# 9_Pwm_Buffer.net
KiCad netlist of a schematic drawn in Altium Designer
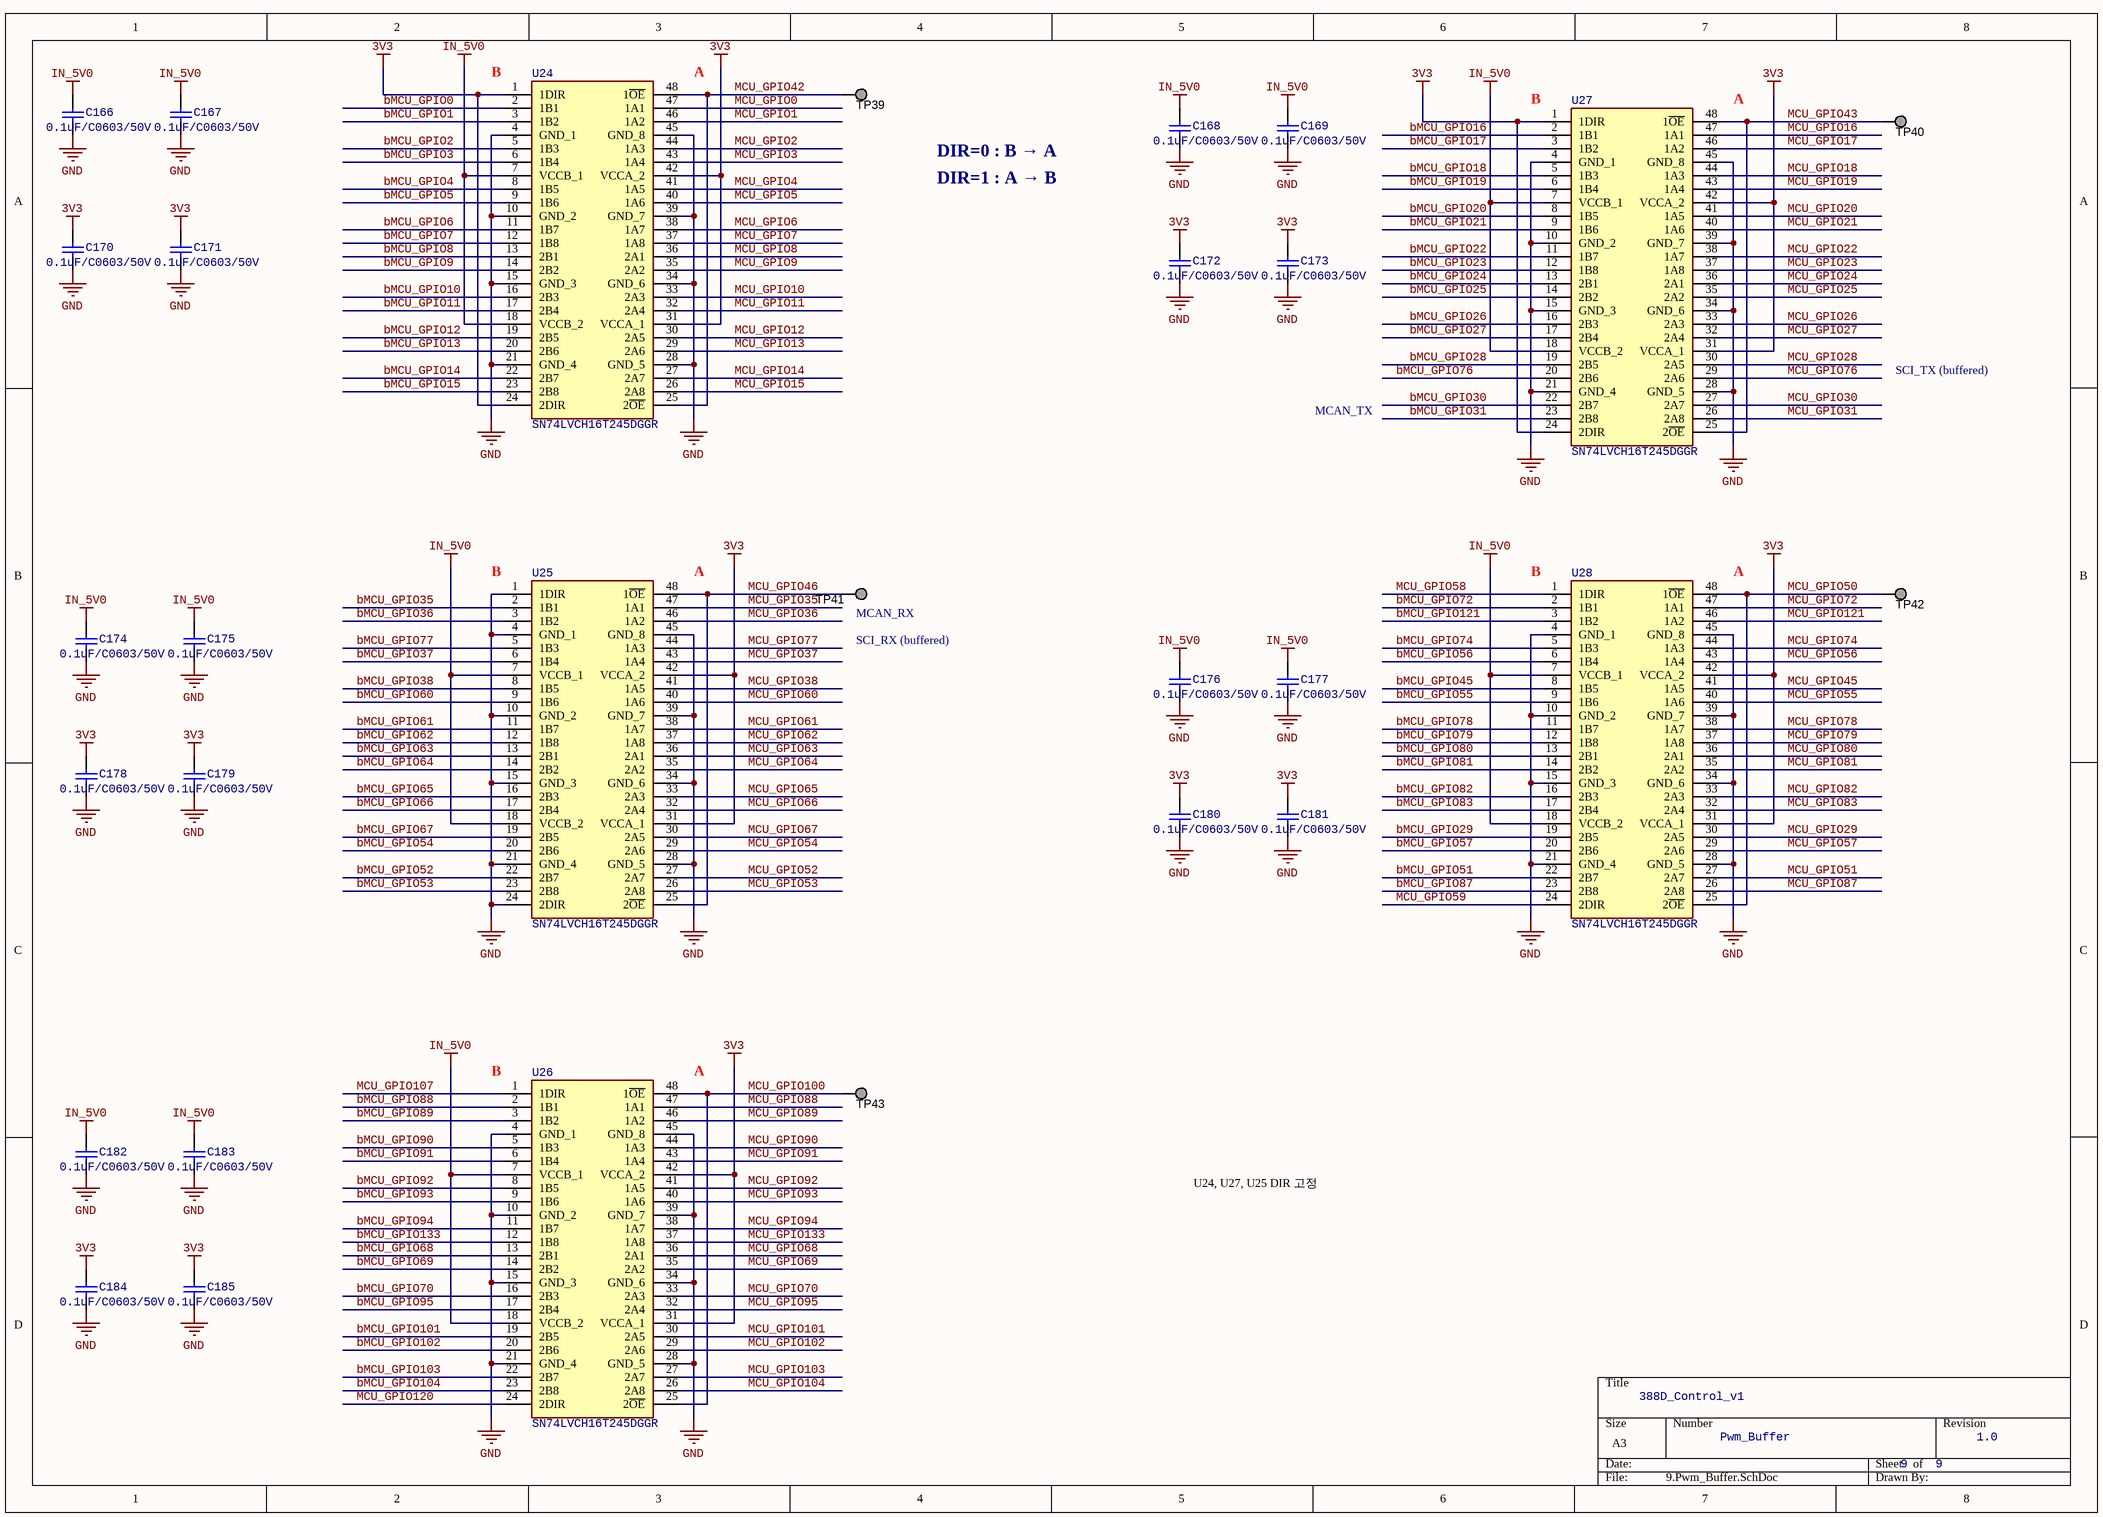
[diagram p0: 9.Pwm_Buffer.SchDoc]

(export (version "E")
  (design (tool "Eeschema 10.0.6"))
  (components
    (comp (ref "C166")
      (value "0.1uF/C0603/50V")
      (footprint "CAPC1608X90X40NL10T20")
      (description "Chip Capacitor, 100 nF, +/- 10%, 50 V, 0603 (1608 Metric)")
      (fields (field (name "TOLERANCE") "10%") (field (name "Comment") "Capacitor 100 nF +/-10% 50 V 0603"))
      (libsource (lib "PEETS_V2") (part "CAP-NP-2"))
    )
    (comp (ref "C167")
      (value "0.1uF/C0603/50V")
      (footprint "CAPC1608X90X40NL10T20")
      (description "Chip Capacitor, 100 nF, +/- 10%, 50 V, 0603 (1608 Metric)")
      (fields (field (name "TOLERANCE") "10%") (field (name "Comment") "Capacitor 100 nF +/-10% 50 V 0603"))
      (libsource (lib "PEETS_V2") (part "CAP-NP-2"))
    )
    (comp (ref "C168")
      (value "0.1uF/C0603/50V")
      (footprint "CAPC1608X90X40NL10T20")
      (description "Chip Capacitor, 100 nF, +/- 10%, 50 V, 0603 (1608 Metric)")
      (fields (field (name "TOLERANCE") "10%") (field (name "Comment") "Capacitor 100 nF +/-10% 50 V 0603"))
      (libsource (lib "PEETS_V2") (part "CAP-NP-2"))
    )
    (comp (ref "C169")
      (value "0.1uF/C0603/50V")
      (footprint "CAPC1608X90X40NL10T20")
      (description "Chip Capacitor, 100 nF, +/- 10%, 50 V, 0603 (1608 Metric)")
      (fields (field (name "TOLERANCE") "10%") (field (name "Comment") "Capacitor 100 nF +/-10% 50 V 0603"))
      (libsource (lib "PEETS_V2") (part "CAP-NP-2"))
    )
    (comp (ref "C170")
      (value "0.1uF/C0603/50V")
      (footprint "CAPC1608X90X40NL10T20")
      (description "Chip Capacitor, 100 nF, +/- 10%, 50 V, 0603 (1608 Metric)")
      (fields (field (name "TOLERANCE") "10%") (field (name "Comment") "Capacitor 100 nF +/-10% 50 V 0603"))
      (libsource (lib "PEETS_V2") (part "CAP-NP-2"))
    )
    (comp (ref "C171")
      (value "0.1uF/C0603/50V")
      (footprint "CAPC1608X90X40NL10T20")
      (description "Chip Capacitor, 100 nF, +/- 10%, 50 V, 0603 (1608 Metric)")
      (fields (field (name "TOLERANCE") "10%") (field (name "Comment") "Capacitor 100 nF +/-10% 50 V 0603"))
      (libsource (lib "PEETS_V2") (part "CAP-NP-2"))
    )
    (comp (ref "C172")
      (value "0.1uF/C0603/50V")
      (footprint "CAPC1608X90X40NL10T20")
      (description "Chip Capacitor, 100 nF, +/- 10%, 50 V, 0603 (1608 Metric)")
      (fields (field (name "TOLERANCE") "10%") (field (name "Comment") "Capacitor 100 nF +/-10% 50 V 0603"))
      (libsource (lib "PEETS_V2") (part "CAP-NP-2"))
    )
    (comp (ref "C173")
      (value "0.1uF/C0603/50V")
      (footprint "CAPC1608X90X40NL10T20")
      (description "Chip Capacitor, 100 nF, +/- 10%, 50 V, 0603 (1608 Metric)")
      (fields (field (name "TOLERANCE") "10%") (field (name "Comment") "Capacitor 100 nF +/-10% 50 V 0603"))
      (libsource (lib "PEETS_V2") (part "CAP-NP-2"))
    )
    (comp (ref "C174")
      (value "0.1uF/C0603/50V")
      (footprint "CAPC1608X90X40NL10T20")
      (description "Chip Capacitor, 100 nF, +/- 10%, 50 V, 0603 (1608 Metric)")
      (fields (field (name "TOLERANCE") "10%") (field (name "Comment") "Capacitor 100 nF +/-10% 50 V 0603"))
      (libsource (lib "PEETS_V2") (part "CAP-NP-2"))
    )
    (comp (ref "C175")
      (value "0.1uF/C0603/50V")
      (footprint "CAPC1608X90X40NL10T20")
      (description "Chip Capacitor, 100 nF, +/- 10%, 50 V, 0603 (1608 Metric)")
      (fields (field (name "TOLERANCE") "10%") (field (name "Comment") "Capacitor 100 nF +/-10% 50 V 0603"))
      (libsource (lib "PEETS_V2") (part "CAP-NP-2"))
    )
    (comp (ref "C176")
      (value "0.1uF/C0603/50V")
      (footprint "CAPC1608X90X40NL10T20")
      (description "Chip Capacitor, 100 nF, +/- 10%, 50 V, 0603 (1608 Metric)")
      (fields (field (name "TOLERANCE") "10%") (field (name "Comment") "Capacitor 100 nF +/-10% 50 V 0603"))
      (libsource (lib "PEETS_V2") (part "CAP-NP-2"))
    )
    (comp (ref "C177")
      (value "0.1uF/C0603/50V")
      (footprint "CAPC1608X90X40NL10T20")
      (description "Chip Capacitor, 100 nF, +/- 10%, 50 V, 0603 (1608 Metric)")
      (fields (field (name "TOLERANCE") "10%") (field (name "Comment") "Capacitor 100 nF +/-10% 50 V 0603"))
      (libsource (lib "PEETS_V2") (part "CAP-NP-2"))
    )
    (comp (ref "C178")
      (value "0.1uF/C0603/50V")
      (footprint "CAPC1608X90X40NL10T20")
      (description "Chip Capacitor, 100 nF, +/- 10%, 50 V, 0603 (1608 Metric)")
      (fields (field (name "TOLERANCE") "10%") (field (name "Comment") "Capacitor 100 nF +/-10% 50 V 0603"))
      (libsource (lib "PEETS_V2") (part "CAP-NP-2"))
    )
    (comp (ref "C179")
      (value "0.1uF/C0603/50V")
      (footprint "CAPC1608X90X40NL10T20")
      (description "Chip Capacitor, 100 nF, +/- 10%, 50 V, 0603 (1608 Metric)")
      (fields (field (name "TOLERANCE") "10%") (field (name "Comment") "Capacitor 100 nF +/-10% 50 V 0603"))
      (libsource (lib "PEETS_V2") (part "CAP-NP-2"))
    )
    (comp (ref "C180")
      (value "0.1uF/C0603/50V")
      (footprint "CAPC1608X90X40NL10T20")
      (description "Chip Capacitor, 100 nF, +/- 10%, 50 V, 0603 (1608 Metric)")
      (fields (field (name "TOLERANCE") "10%") (field (name "Comment") "Capacitor 100 nF +/-10% 50 V 0603"))
      (libsource (lib "PEETS_V2") (part "CAP-NP-2"))
    )
    (comp (ref "C181")
      (value "0.1uF/C0603/50V")
      (footprint "CAPC1608X90X40NL10T20")
      (description "Chip Capacitor, 100 nF, +/- 10%, 50 V, 0603 (1608 Metric)")
      (fields (field (name "TOLERANCE") "10%") (field (name "Comment") "Capacitor 100 nF +/-10% 50 V 0603"))
      (libsource (lib "PEETS_V2") (part "CAP-NP-2"))
    )
    (comp (ref "C182")
      (value "0.1uF/C0603/50V")
      (footprint "CAPC1608X90X40NL10T20")
      (description "Chip Capacitor, 100 nF, +/- 10%, 50 V, 0603 (1608 Metric)")
      (fields (field (name "TOLERANCE") "10%") (field (name "Comment") "Capacitor 100 nF +/-10% 50 V 0603"))
      (libsource (lib "PEETS_V2") (part "CAP-NP-2"))
    )
    (comp (ref "C183")
      (value "0.1uF/C0603/50V")
      (footprint "CAPC1608X90X40NL10T20")
      (description "Chip Capacitor, 100 nF, +/- 10%, 50 V, 0603 (1608 Metric)")
      (fields (field (name "TOLERANCE") "10%") (field (name "Comment") "Capacitor 100 nF +/-10% 50 V 0603"))
      (libsource (lib "PEETS_V2") (part "CAP-NP-2"))
    )
    (comp (ref "C184")
      (value "0.1uF/C0603/50V")
      (footprint "CAPC1608X90X40NL10T20")
      (description "Chip Capacitor, 100 nF, +/- 10%, 50 V, 0603 (1608 Metric)")
      (fields (field (name "TOLERANCE") "10%") (field (name "Comment") "Capacitor 100 nF +/-10% 50 V 0603"))
      (libsource (lib "PEETS_V2") (part "CAP-NP-2"))
    )
    (comp (ref "C185")
      (value "0.1uF/C0603/50V")
      (footprint "CAPC1608X90X40NL10T20")
      (description "Chip Capacitor, 100 nF, +/- 10%, 50 V, 0603 (1608 Metric)")
      (fields (field (name "TOLERANCE") "10%") (field (name "Comment") "Capacitor 100 nF +/-10% 50 V 0603"))
      (libsource (lib "PEETS_V2") (part "CAP-NP-2"))
    )
    (comp (ref "TP39")
      (value "TESTPOINT")
      (footprint "TP_50MIL-25MILHOLE")
      (description "TEST POINT.  No entry in BOM.")
      (libsource (lib "388D_Control_v1") (part "CMP-0078143-3"))
    )
    (comp (ref "TP40")
      (value "TESTPOINT")
      (footprint "TP_50MIL-25MILHOLE")
      (description "TEST POINT.  No entry in BOM.")
      (libsource (lib "388D_Control_v1") (part "CMP-0078143-3"))
    )
    (comp (ref "TP41")
      (value "TESTPOINT")
      (footprint "TP_50MIL-25MILHOLE")
      (description "TEST POINT.  No entry in BOM.")
      (libsource (lib "388D_Control_v1") (part "CMP-0078143-3"))
    )
    (comp (ref "TP42")
      (value "TESTPOINT")
      (footprint "TP_50MIL-25MILHOLE")
      (description "TEST POINT.  No entry in BOM.")
      (libsource (lib "388D_Control_v1") (part "CMP-0078143-3"))
    )
    (comp (ref "TP43")
      (value "TESTPOINT")
      (footprint "TP_50MIL-25MILHOLE")
      (description "TEST POINT.  No entry in BOM.")
      (libsource (lib "388D_Control_v1") (part "CMP-0078143-3"))
    )
    (comp (ref "U24")
      (value "SN74LVCH16T245DGGR")
      (footprint "SOP50P810X120-48N")
      (description "16-Bit Dual-Supply Bus Transceiver")
      (fields (field (name "MOUSER PART NUMBER") "595-SN74LVCH16T245GR"))
      (libsource (lib "PEETS_V2") (part "SN74LVCH16T245DGGR"))
    )
    (comp (ref "U25")
      (value "SN74LVCH16T245DGGR")
      (footprint "SOP50P810X120-48N")
      (description "16-Bit Dual-Supply Bus Transceiver")
      (fields (field (name "MOUSER PART NUMBER") "595-SN74LVCH16T245GR"))
      (libsource (lib "PEETS_V2") (part "SN74LVCH16T245DGGR"))
    )
    (comp (ref "U26")
      (value "SN74LVCH16T245DGGR")
      (footprint "SOP50P810X120-48N")
      (description "16-Bit Dual-Supply Bus Transceiver")
      (fields (field (name "MOUSER PART NUMBER") "595-SN74LVCH16T245GR"))
      (libsource (lib "PEETS_V2") (part "SN74LVCH16T245DGGR"))
    )
    (comp (ref "U27")
      (value "SN74LVCH16T245DGGR")
      (footprint "SOP50P810X120-48N")
      (description "16-Bit Dual-Supply Bus Transceiver")
      (fields (field (name "MOUSER PART NUMBER") "595-SN74LVCH16T245GR"))
      (libsource (lib "PEETS_V2") (part "SN74LVCH16T245DGGR"))
    )
    (comp (ref "U28")
      (value "SN74LVCH16T245DGGR")
      (footprint "SOP50P810X120-48N")
      (description "16-Bit Dual-Supply Bus Transceiver")
      (fields (field (name "MOUSER PART NUMBER") "595-SN74LVCH16T245GR"))
      (libsource (lib "PEETS_V2") (part "SN74LVCH16T245DGGR"))
    )
  )
  (nets
    (net (code "1") (name "/MCU_GPIO0") (class "Default")
      (node (ref "U24") (pin "47") (pinfunction "1A1_47") (pintype "passive"))
    )
    (net (code "2") (name "/MCU_GPIO1") (class "Default")
      (node (ref "U24") (pin "46") (pinfunction "1A2_46") (pintype "passive"))
    )
    (net (code "3") (name "/MCU_GPIO2") (class "Default")
      (node (ref "U24") (pin "44") (pinfunction "1A3_44") (pintype "passive"))
    )
    (net (code "4") (name "/MCU_GPIO3") (class "Default")
      (node (ref "U24") (pin "43") (pinfunction "1A4_43") (pintype "passive"))
    )
    (net (code "5") (name "/MCU_GPIO4") (class "Default")
      (node (ref "U24") (pin "41") (pinfunction "1A5_41") (pintype "passive"))
    )
    (net (code "6") (name "/MCU_GPIO5") (class "Default")
      (node (ref "U24") (pin "40") (pinfunction "1A6_40") (pintype "passive"))
    )
    (net (code "7") (name "/MCU_GPIO6") (class "Default")
      (node (ref "U24") (pin "38") (pinfunction "1A7_38") (pintype "passive"))
    )
    (net (code "8") (name "/MCU_GPIO7") (class "Default")
      (node (ref "U24") (pin "37") (pinfunction "1A8_37") (pintype "passive"))
    )
    (net (code "9") (name "/MCU_GPIO8") (class "Default")
      (node (ref "U24") (pin "36") (pinfunction "2A1_36") (pintype "passive"))
    )
    (net (code "10") (name "/MCU_GPIO9") (class "Default")
      (node (ref "U24") (pin "35") (pinfunction "2A2_35") (pintype "passive"))
    )
    (net (code "11") (name "/MCU_GPIO10") (class "Default")
      (node (ref "U24") (pin "33") (pinfunction "2A3_33") (pintype "passive"))
    )
    (net (code "12") (name "/MCU_GPIO11") (class "Default")
      (node (ref "U24") (pin "32") (pinfunction "2A4_32") (pintype "passive"))
    )
    (net (code "13") (name "/MCU_GPIO12") (class "Default")
      (node (ref "U24") (pin "30") (pinfunction "2A5_30") (pintype "passive"))
    )
    (net (code "14") (name "/MCU_GPIO13") (class "Default")
      (node (ref "U24") (pin "29") (pinfunction "2A6_29") (pintype "passive"))
    )
    (net (code "15") (name "/MCU_GPIO14") (class "Default")
      (node (ref "U24") (pin "27") (pinfunction "2A7_27") (pintype "passive"))
    )
    (net (code "16") (name "/MCU_GPIO15") (class "Default")
      (node (ref "U24") (pin "26") (pinfunction "2A8_26") (pintype "passive"))
    )
    (net (code "17") (name "/MCU_GPIO16") (class "Default")
      (node (ref "U27") (pin "47") (pinfunction "1A1_47") (pintype "passive"))
    )
    (net (code "18") (name "/MCU_GPIO17") (class "Default")
      (node (ref "U27") (pin "46") (pinfunction "1A2_46") (pintype "passive"))
    )
    (net (code "19") (name "/MCU_GPIO18") (class "Default")
      (node (ref "U27") (pin "44") (pinfunction "1A3_44") (pintype "passive"))
    )
    (net (code "20") (name "/MCU_GPIO19") (class "Default")
      (node (ref "U27") (pin "43") (pinfunction "1A4_43") (pintype "passive"))
    )
    (net (code "21") (name "/MCU_GPIO20") (class "Default")
      (node (ref "U27") (pin "41") (pinfunction "1A5_41") (pintype "passive"))
    )
    (net (code "22") (name "/MCU_GPIO21") (class "Default")
      (node (ref "U27") (pin "40") (pinfunction "1A6_40") (pintype "passive"))
    )
    (net (code "23") (name "/MCU_GPIO22") (class "Default")
      (node (ref "U27") (pin "38") (pinfunction "1A7_38") (pintype "passive"))
    )
    (net (code "24") (name "/MCU_GPIO23") (class "Default")
      (node (ref "U27") (pin "37") (pinfunction "1A8_37") (pintype "passive"))
    )
    (net (code "25") (name "/MCU_GPIO24") (class "Default")
      (node (ref "U27") (pin "36") (pinfunction "2A1_36") (pintype "passive"))
    )
    (net (code "26") (name "/MCU_GPIO25") (class "Default")
      (node (ref "U27") (pin "35") (pinfunction "2A2_35") (pintype "passive"))
    )
    (net (code "27") (name "/MCU_GPIO26") (class "Default")
      (node (ref "U27") (pin "33") (pinfunction "2A3_33") (pintype "passive"))
    )
    (net (code "28") (name "/MCU_GPIO27") (class "Default")
      (node (ref "U27") (pin "32") (pinfunction "2A4_32") (pintype "passive"))
    )
    (net (code "29") (name "/MCU_GPIO28") (class "Default")
      (node (ref "U27") (pin "30") (pinfunction "2A5_30") (pintype "passive"))
    )
    (net (code "30") (name "/MCU_GPIO29") (class "Default")
      (node (ref "U28") (pin "30") (pinfunction "2A5_30") (pintype "passive"))
    )
    (net (code "31") (name "/MCU_GPIO30") (class "Default")
      (node (ref "U27") (pin "27") (pinfunction "2A7_27") (pintype "passive"))
    )
    (net (code "32") (name "/MCU_GPIO31") (class "Default")
      (node (ref "U27") (pin "26") (pinfunction "2A8_26") (pintype "passive"))
    )
    (net (code "33") (name "/MCU_GPIO35") (class "Default")
      (node (ref "U25") (pin "47") (pinfunction "1A1_47") (pintype "passive"))
    )
    (net (code "34") (name "/MCU_GPIO36") (class "Default")
      (node (ref "U25") (pin "46") (pinfunction "1A2_46") (pintype "passive"))
    )
    (net (code "35") (name "/MCU_GPIO37") (class "Default")
      (node (ref "U25") (pin "43") (pinfunction "1A4_43") (pintype "passive"))
    )
    (net (code "36") (name "/MCU_GPIO38") (class "Default")
      (node (ref "U25") (pin "41") (pinfunction "1A5_41") (pintype "passive"))
    )
    (net (code "37") (name "/MCU_GPIO42") (class "Default")
      (node (ref "TP39") (pin "1") (pintype "passive"))
      (node (ref "U24") (pin "25") (pinfunction "2~{OE}_25") (pintype "passive"))
      (node (ref "U24") (pin "48") (pinfunction "1~{OE}_48") (pintype "passive"))
    )
    (net (code "38") (name "/MCU_GPIO43") (class "Default")
      (node (ref "TP40") (pin "1") (pintype "passive"))
      (node (ref "U27") (pin "25") (pinfunction "2~{OE}_25") (pintype "passive"))
      (node (ref "U27") (pin "48") (pinfunction "1~{OE}_48") (pintype "passive"))
    )
    (net (code "39") (name "/MCU_GPIO45") (class "Default")
      (node (ref "U28") (pin "41") (pinfunction "1A5_41") (pintype "passive"))
    )
    (net (code "40") (name "/MCU_GPIO46") (class "Default")
      (node (ref "TP41") (pin "1") (pintype "passive"))
      (node (ref "U25") (pin "25") (pinfunction "2~{OE}_25") (pintype "passive"))
      (node (ref "U25") (pin "48") (pinfunction "1~{OE}_48") (pintype "passive"))
    )
    (net (code "41") (name "/MCU_GPIO50") (class "Default")
      (node (ref "TP42") (pin "1") (pintype "passive"))
      (node (ref "U28") (pin "25") (pinfunction "2~{OE}_25") (pintype "passive"))
      (node (ref "U28") (pin "48") (pinfunction "1~{OE}_48") (pintype "passive"))
    )
    (net (code "42") (name "/MCU_GPIO51") (class "Default")
      (node (ref "U28") (pin "27") (pinfunction "2A7_27") (pintype "passive"))
    )
    (net (code "43") (name "/MCU_GPIO52") (class "Default")
      (node (ref "U25") (pin "27") (pinfunction "2A7_27") (pintype "passive"))
    )
    (net (code "44") (name "/MCU_GPIO53") (class "Default")
      (node (ref "U25") (pin "26") (pinfunction "2A8_26") (pintype "passive"))
    )
    (net (code "45") (name "/MCU_GPIO54") (class "Default")
      (node (ref "U25") (pin "29") (pinfunction "2A6_29") (pintype "passive"))
    )
    (net (code "46") (name "/MCU_GPIO55") (class "Default")
      (node (ref "U28") (pin "40") (pinfunction "1A6_40") (pintype "passive"))
    )
    (net (code "47") (name "/MCU_GPIO56") (class "Default")
      (node (ref "U28") (pin "43") (pinfunction "1A4_43") (pintype "passive"))
    )
    (net (code "48") (name "/MCU_GPIO57") (class "Default")
      (node (ref "U28") (pin "29") (pinfunction "2A6_29") (pintype "passive"))
    )
    (net (code "49") (name "/MCU_GPIO58") (class "Default")
      (node (ref "U28") (pin "1") (pinfunction "1DIR_1") (pintype "passive"))
    )
    (net (code "50") (name "/MCU_GPIO59") (class "Default")
      (node (ref "U28") (pin "24") (pinfunction "2DIR_24") (pintype "passive"))
    )
    (net (code "51") (name "/MCU_GPIO60") (class "Default")
      (node (ref "U25") (pin "40") (pinfunction "1A6_40") (pintype "passive"))
    )
    (net (code "52") (name "/MCU_GPIO61") (class "Default")
      (node (ref "U25") (pin "38") (pinfunction "1A7_38") (pintype "passive"))
    )
    (net (code "53") (name "/MCU_GPIO62") (class "Default")
      (node (ref "U25") (pin "37") (pinfunction "1A8_37") (pintype "passive"))
    )
    (net (code "54") (name "/MCU_GPIO63") (class "Default")
      (node (ref "U25") (pin "36") (pinfunction "2A1_36") (pintype "passive"))
    )
    (net (code "55") (name "/MCU_GPIO64") (class "Default")
      (node (ref "U25") (pin "35") (pinfunction "2A2_35") (pintype "passive"))
    )
    (net (code "56") (name "/MCU_GPIO65") (class "Default")
      (node (ref "U25") (pin "33") (pinfunction "2A3_33") (pintype "passive"))
    )
    (net (code "57") (name "/MCU_GPIO66") (class "Default")
      (node (ref "U25") (pin "32") (pinfunction "2A4_32") (pintype "passive"))
    )
    (net (code "58") (name "/MCU_GPIO67") (class "Default")
      (node (ref "U25") (pin "30") (pinfunction "2A5_30") (pintype "passive"))
    )
    (net (code "59") (name "/MCU_GPIO68") (class "Default")
      (node (ref "U26") (pin "36") (pinfunction "2A1_36") (pintype "passive"))
    )
    (net (code "60") (name "/MCU_GPIO69") (class "Default")
      (node (ref "U26") (pin "35") (pinfunction "2A2_35") (pintype "passive"))
    )
    (net (code "61") (name "/MCU_GPIO70") (class "Default")
      (node (ref "U26") (pin "33") (pinfunction "2A3_33") (pintype "passive"))
    )
    (net (code "62") (name "/MCU_GPIO72") (class "Default")
      (node (ref "U28") (pin "47") (pinfunction "1A1_47") (pintype "passive"))
    )
    (net (code "63") (name "/MCU_GPIO74") (class "Default")
      (node (ref "U28") (pin "44") (pinfunction "1A3_44") (pintype "passive"))
    )
    (net (code "64") (name "/MCU_GPIO76") (class "Default")
      (node (ref "U27") (pin "29") (pinfunction "2A6_29") (pintype "passive"))
    )
    (net (code "65") (name "/MCU_GPIO77") (class "Default")
      (node (ref "U25") (pin "44") (pinfunction "1A3_44") (pintype "passive"))
    )
    (net (code "66") (name "/MCU_GPIO78") (class "Default")
      (node (ref "U28") (pin "38") (pinfunction "1A7_38") (pintype "passive"))
    )
    (net (code "67") (name "/MCU_GPIO79") (class "Default")
      (node (ref "U28") (pin "37") (pinfunction "1A8_37") (pintype "passive"))
    )
    (net (code "68") (name "/MCU_GPIO80") (class "Default")
      (node (ref "U28") (pin "36") (pinfunction "2A1_36") (pintype "passive"))
    )
    (net (code "69") (name "/MCU_GPIO81") (class "Default")
      (node (ref "U28") (pin "35") (pinfunction "2A2_35") (pintype "passive"))
    )
    (net (code "70") (name "/MCU_GPIO82") (class "Default")
      (node (ref "U28") (pin "33") (pinfunction "2A3_33") (pintype "passive"))
    )
    (net (code "71") (name "/MCU_GPIO83") (class "Default")
      (node (ref "U28") (pin "32") (pinfunction "2A4_32") (pintype "passive"))
    )
    (net (code "72") (name "/MCU_GPIO87") (class "Default")
      (node (ref "U28") (pin "26") (pinfunction "2A8_26") (pintype "passive"))
    )
    (net (code "73") (name "/MCU_GPIO88") (class "Default")
      (node (ref "U26") (pin "47") (pinfunction "1A1_47") (pintype "passive"))
    )
    (net (code "74") (name "/MCU_GPIO89") (class "Default")
      (node (ref "U26") (pin "46") (pinfunction "1A2_46") (pintype "passive"))
    )
    (net (code "75") (name "/MCU_GPIO90") (class "Default")
      (node (ref "U26") (pin "44") (pinfunction "1A3_44") (pintype "passive"))
    )
    (net (code "76") (name "/MCU_GPIO91") (class "Default")
      (node (ref "U26") (pin "43") (pinfunction "1A4_43") (pintype "passive"))
    )
    (net (code "77") (name "/MCU_GPIO92") (class "Default")
      (node (ref "U26") (pin "41") (pinfunction "1A5_41") (pintype "passive"))
    )
    (net (code "78") (name "/MCU_GPIO93") (class "Default")
      (node (ref "U26") (pin "40") (pinfunction "1A6_40") (pintype "passive"))
    )
    (net (code "79") (name "/MCU_GPIO94") (class "Default")
      (node (ref "U26") (pin "38") (pinfunction "1A7_38") (pintype "passive"))
    )
    (net (code "80") (name "/MCU_GPIO95") (class "Default")
      (node (ref "U26") (pin "32") (pinfunction "2A4_32") (pintype "passive"))
    )
    (net (code "81") (name "/MCU_GPIO100") (class "Default")
      (node (ref "TP43") (pin "1") (pintype "passive"))
      (node (ref "U26") (pin "25") (pinfunction "2~{OE}_25") (pintype "passive"))
      (node (ref "U26") (pin "48") (pinfunction "1~{OE}_48") (pintype "passive"))
    )
    (net (code "82") (name "/MCU_GPIO101") (class "Default")
      (node (ref "U26") (pin "30") (pinfunction "2A5_30") (pintype "passive"))
    )
    (net (code "83") (name "/MCU_GPIO102") (class "Default")
      (node (ref "U26") (pin "29") (pinfunction "2A6_29") (pintype "passive"))
    )
    (net (code "84") (name "/MCU_GPIO103") (class "Default")
      (node (ref "U26") (pin "27") (pinfunction "2A7_27") (pintype "passive"))
    )
    (net (code "85") (name "/MCU_GPIO104") (class "Default")
      (node (ref "U26") (pin "26") (pinfunction "2A8_26") (pintype "passive"))
    )
    (net (code "86") (name "/MCU_GPIO107") (class "Default")
      (node (ref "U26") (pin "1") (pinfunction "1DIR_1") (pintype "passive"))
    )
    (net (code "87") (name "/MCU_GPIO120") (class "Default")
      (node (ref "U26") (pin "24") (pinfunction "2DIR_24") (pintype "passive"))
    )
    (net (code "88") (name "/MCU_GPIO121") (class "Default")
      (node (ref "U28") (pin "46") (pinfunction "1A2_46") (pintype "passive"))
    )
    (net (code "89") (name "/MCU_GPIO133") (class "Default")
      (node (ref "U26") (pin "37") (pinfunction "1A8_37") (pintype "passive"))
    )
    (net (code "90") (name "/bMCU_GPIO0") (class "Default")
      (node (ref "U24") (pin "2") (pinfunction "1B1_2") (pintype "passive"))
    )
    (net (code "91") (name "/bMCU_GPIO1") (class "Default")
      (node (ref "U24") (pin "3") (pinfunction "1B2_3") (pintype "passive"))
    )
    (net (code "92") (name "/bMCU_GPIO2") (class "Default")
      (node (ref "U24") (pin "5") (pinfunction "1B3_5") (pintype "passive"))
    )
    (net (code "93") (name "/bMCU_GPIO3") (class "Default")
      (node (ref "U24") (pin "6") (pinfunction "1B4_6") (pintype "passive"))
    )
    (net (code "94") (name "/bMCU_GPIO4") (class "Default")
      (node (ref "U24") (pin "8") (pinfunction "1B5_8") (pintype "passive"))
    )
    (net (code "95") (name "/bMCU_GPIO5") (class "Default")
      (node (ref "U24") (pin "9") (pinfunction "1B6_9") (pintype "passive"))
    )
    (net (code "96") (name "/bMCU_GPIO6") (class "Default")
      (node (ref "U24") (pin "11") (pinfunction "1B7_11") (pintype "passive"))
    )
    (net (code "97") (name "/bMCU_GPIO7") (class "Default")
      (node (ref "U24") (pin "12") (pinfunction "1B8_12") (pintype "passive"))
    )
    (net (code "98") (name "/bMCU_GPIO8") (class "Default")
      (node (ref "U24") (pin "13") (pinfunction "2B1_13") (pintype "passive"))
    )
    (net (code "99") (name "/bMCU_GPIO9") (class "Default")
      (node (ref "U24") (pin "14") (pinfunction "2B2_14") (pintype "passive"))
    )
    (net (code "100") (name "/bMCU_GPIO10") (class "Default")
      (node (ref "U24") (pin "16") (pinfunction "2B3_16") (pintype "passive"))
    )
    (net (code "101") (name "/bMCU_GPIO11") (class "Default")
      (node (ref "U24") (pin "17") (pinfunction "2B4_17") (pintype "passive"))
    )
    (net (code "102") (name "/bMCU_GPIO12") (class "Default")
      (node (ref "U24") (pin "19") (pinfunction "2B5_19") (pintype "passive"))
    )
    (net (code "103") (name "/bMCU_GPIO13") (class "Default")
      (node (ref "U24") (pin "20") (pinfunction "2B6_20") (pintype "passive"))
    )
    (net (code "104") (name "/bMCU_GPIO14") (class "Default")
      (node (ref "U24") (pin "22") (pinfunction "2B7_22") (pintype "passive"))
    )
    (net (code "105") (name "/bMCU_GPIO15") (class "Default")
      (node (ref "U24") (pin "23") (pinfunction "2B8_23") (pintype "passive"))
    )
    (net (code "106") (name "/bMCU_GPIO16") (class "Default")
      (node (ref "U27") (pin "2") (pinfunction "1B1_2") (pintype "passive"))
    )
    (net (code "107") (name "/bMCU_GPIO17") (class "Default")
      (node (ref "U27") (pin "3") (pinfunction "1B2_3") (pintype "passive"))
    )
    (net (code "108") (name "/bMCU_GPIO18") (class "Default")
      (node (ref "U27") (pin "5") (pinfunction "1B3_5") (pintype "passive"))
    )
    (net (code "109") (name "/bMCU_GPIO19") (class "Default")
      (node (ref "U27") (pin "6") (pinfunction "1B4_6") (pintype "passive"))
    )
    (net (code "110") (name "/bMCU_GPIO20") (class "Default")
      (node (ref "U27") (pin "8") (pinfunction "1B5_8") (pintype "passive"))
    )
    (net (code "111") (name "/bMCU_GPIO21") (class "Default")
      (node (ref "U27") (pin "9") (pinfunction "1B6_9") (pintype "passive"))
    )
    (net (code "112") (name "/bMCU_GPIO22") (class "Default")
      (node (ref "U27") (pin "11") (pinfunction "1B7_11") (pintype "passive"))
    )
    (net (code "113") (name "/bMCU_GPIO23") (class "Default")
      (node (ref "U27") (pin "12") (pinfunction "1B8_12") (pintype "passive"))
    )
    (net (code "114") (name "/bMCU_GPIO24") (class "Default")
      (node (ref "U27") (pin "13") (pinfunction "2B1_13") (pintype "passive"))
    )
    (net (code "115") (name "/bMCU_GPIO25") (class "Default")
      (node (ref "U27") (pin "14") (pinfunction "2B2_14") (pintype "passive"))
    )
    (net (code "116") (name "/bMCU_GPIO26") (class "Default")
      (node (ref "U27") (pin "16") (pinfunction "2B3_16") (pintype "passive"))
    )
    (net (code "117") (name "/bMCU_GPIO27") (class "Default")
      (node (ref "U27") (pin "17") (pinfunction "2B4_17") (pintype "passive"))
    )
    (net (code "118") (name "/bMCU_GPIO28") (class "Default")
      (node (ref "U27") (pin "19") (pinfunction "2B5_19") (pintype "passive"))
    )
    (net (code "119") (name "/bMCU_GPIO29") (class "Default")
      (node (ref "U28") (pin "19") (pinfunction "2B5_19") (pintype "passive"))
    )
    (net (code "120") (name "/bMCU_GPIO30") (class "Default")
      (node (ref "U27") (pin "22") (pinfunction "2B7_22") (pintype "passive"))
    )
    (net (code "121") (name "/bMCU_GPIO31") (class "Default")
      (node (ref "U27") (pin "23") (pinfunction "2B8_23") (pintype "passive"))
    )
    (net (code "122") (name "/bMCU_GPIO35") (class "Default")
      (node (ref "U25") (pin "2") (pinfunction "1B1_2") (pintype "passive"))
    )
    (net (code "123") (name "/bMCU_GPIO36") (class "Default")
      (node (ref "U25") (pin "3") (pinfunction "1B2_3") (pintype "passive"))
    )
    (net (code "124") (name "/bMCU_GPIO37") (class "Default")
      (node (ref "U25") (pin "6") (pinfunction "1B4_6") (pintype "passive"))
    )
    (net (code "125") (name "/bMCU_GPIO38") (class "Default")
      (node (ref "U25") (pin "8") (pinfunction "1B5_8") (pintype "passive"))
    )
    (net (code "126") (name "/bMCU_GPIO45") (class "Default")
      (node (ref "U28") (pin "8") (pinfunction "1B5_8") (pintype "passive"))
    )
    (net (code "127") (name "/bMCU_GPIO51") (class "Default")
      (node (ref "U28") (pin "22") (pinfunction "2B7_22") (pintype "passive"))
    )
    (net (code "128") (name "/bMCU_GPIO52") (class "Default")
      (node (ref "U25") (pin "22") (pinfunction "2B7_22") (pintype "passive"))
    )
    (net (code "129") (name "/bMCU_GPIO53") (class "Default")
      (node (ref "U25") (pin "23") (pinfunction "2B8_23") (pintype "passive"))
    )
    (net (code "130") (name "/bMCU_GPIO54") (class "Default")
      (node (ref "U25") (pin "20") (pinfunction "2B6_20") (pintype "passive"))
    )
    (net (code "131") (name "/bMCU_GPIO55") (class "Default")
      (node (ref "U28") (pin "9") (pinfunction "1B6_9") (pintype "passive"))
    )
    (net (code "132") (name "/bMCU_GPIO56") (class "Default")
      (node (ref "U28") (pin "6") (pinfunction "1B4_6") (pintype "passive"))
    )
    (net (code "133") (name "/bMCU_GPIO57") (class "Default")
      (node (ref "U28") (pin "20") (pinfunction "2B6_20") (pintype "passive"))
    )
    (net (code "134") (name "/bMCU_GPIO60") (class "Default")
      (node (ref "U25") (pin "9") (pinfunction "1B6_9") (pintype "passive"))
    )
    (net (code "135") (name "/bMCU_GPIO61") (class "Default")
      (node (ref "U25") (pin "11") (pinfunction "1B7_11") (pintype "passive"))
    )
    (net (code "136") (name "/bMCU_GPIO62") (class "Default")
      (node (ref "U25") (pin "12") (pinfunction "1B8_12") (pintype "passive"))
    )
    (net (code "137") (name "/bMCU_GPIO63") (class "Default")
      (node (ref "U25") (pin "13") (pinfunction "2B1_13") (pintype "passive"))
    )
    (net (code "138") (name "/bMCU_GPIO64") (class "Default")
      (node (ref "U25") (pin "14") (pinfunction "2B2_14") (pintype "passive"))
    )
    (net (code "139") (name "/bMCU_GPIO65") (class "Default")
      (node (ref "U25") (pin "16") (pinfunction "2B3_16") (pintype "passive"))
    )
    (net (code "140") (name "/bMCU_GPIO66") (class "Default")
      (node (ref "U25") (pin "17") (pinfunction "2B4_17") (pintype "passive"))
    )
    (net (code "141") (name "/bMCU_GPIO67") (class "Default")
      (node (ref "U25") (pin "19") (pinfunction "2B5_19") (pintype "passive"))
    )
    (net (code "142") (name "/bMCU_GPIO68") (class "Default")
      (node (ref "U26") (pin "13") (pinfunction "2B1_13") (pintype "passive"))
    )
    (net (code "143") (name "/bMCU_GPIO69") (class "Default")
      (node (ref "U26") (pin "14") (pinfunction "2B2_14") (pintype "passive"))
    )
    (net (code "144") (name "/bMCU_GPIO70") (class "Default")
      (node (ref "U26") (pin "16") (pinfunction "2B3_16") (pintype "passive"))
    )
    (net (code "145") (name "/bMCU_GPIO72") (class "Default")
      (node (ref "U28") (pin "2") (pinfunction "1B1_2") (pintype "passive"))
    )
    (net (code "146") (name "/bMCU_GPIO74") (class "Default")
      (node (ref "U28") (pin "5") (pinfunction "1B3_5") (pintype "passive"))
    )
    (net (code "147") (name "/bMCU_GPIO76") (class "Default")
      (node (ref "U27") (pin "20") (pinfunction "2B6_20") (pintype "passive"))
    )
    (net (code "148") (name "/bMCU_GPIO77") (class "Default")
      (node (ref "U25") (pin "5") (pinfunction "1B3_5") (pintype "passive"))
    )
    (net (code "149") (name "/bMCU_GPIO78") (class "Default")
      (node (ref "U28") (pin "11") (pinfunction "1B7_11") (pintype "passive"))
    )
    (net (code "150") (name "/bMCU_GPIO79") (class "Default")
      (node (ref "U28") (pin "12") (pinfunction "1B8_12") (pintype "passive"))
    )
    (net (code "151") (name "/bMCU_GPIO80") (class "Default")
      (node (ref "U28") (pin "13") (pinfunction "2B1_13") (pintype "passive"))
    )
    (net (code "152") (name "/bMCU_GPIO81") (class "Default")
      (node (ref "U28") (pin "14") (pinfunction "2B2_14") (pintype "passive"))
    )
    (net (code "153") (name "/bMCU_GPIO82") (class "Default")
      (node (ref "U28") (pin "16") (pinfunction "2B3_16") (pintype "passive"))
    )
    (net (code "154") (name "/bMCU_GPIO83") (class "Default")
      (node (ref "U28") (pin "17") (pinfunction "2B4_17") (pintype "passive"))
    )
    (net (code "155") (name "/bMCU_GPIO87") (class "Default")
      (node (ref "U28") (pin "23") (pinfunction "2B8_23") (pintype "passive"))
    )
    (net (code "156") (name "/bMCU_GPIO88") (class "Default")
      (node (ref "U26") (pin "2") (pinfunction "1B1_2") (pintype "passive"))
    )
    (net (code "157") (name "/bMCU_GPIO89") (class "Default")
      (node (ref "U26") (pin "3") (pinfunction "1B2_3") (pintype "passive"))
    )
    (net (code "158") (name "/bMCU_GPIO90") (class "Default")
      (node (ref "U26") (pin "5") (pinfunction "1B3_5") (pintype "passive"))
    )
    (net (code "159") (name "/bMCU_GPIO91") (class "Default")
      (node (ref "U26") (pin "6") (pinfunction "1B4_6") (pintype "passive"))
    )
    (net (code "160") (name "/bMCU_GPIO92") (class "Default")
      (node (ref "U26") (pin "8") (pinfunction "1B5_8") (pintype "passive"))
    )
    (net (code "161") (name "/bMCU_GPIO93") (class "Default")
      (node (ref "U26") (pin "9") (pinfunction "1B6_9") (pintype "passive"))
    )
    (net (code "162") (name "/bMCU_GPIO94") (class "Default")
      (node (ref "U26") (pin "11") (pinfunction "1B7_11") (pintype "passive"))
    )
    (net (code "163") (name "/bMCU_GPIO95") (class "Default")
      (node (ref "U26") (pin "17") (pinfunction "2B4_17") (pintype "passive"))
    )
    (net (code "164") (name "/bMCU_GPIO101") (class "Default")
      (node (ref "U26") (pin "19") (pinfunction "2B5_19") (pintype "passive"))
    )
    (net (code "165") (name "/bMCU_GPIO102") (class "Default")
      (node (ref "U26") (pin "20") (pinfunction "2B6_20") (pintype "passive"))
    )
    (net (code "166") (name "/bMCU_GPIO103") (class "Default")
      (node (ref "U26") (pin "22") (pinfunction "2B7_22") (pintype "passive"))
    )
    (net (code "167") (name "/bMCU_GPIO104") (class "Default")
      (node (ref "U26") (pin "23") (pinfunction "2B8_23") (pintype "passive"))
    )
    (net (code "168") (name "/bMCU_GPIO121") (class "Default")
      (node (ref "U28") (pin "3") (pinfunction "1B2_3") (pintype "passive"))
    )
    (net (code "169") (name "/bMCU_GPIO133") (class "Default")
      (node (ref "U26") (pin "12") (pinfunction "1B8_12") (pintype "passive"))
    )
    (net (code "170") (name "3V3") (class "Default")
      (node (ref "C170") (pin "1") (pinfunction "1_1") (pintype "passive"))
      (node (ref "C171") (pin "1") (pinfunction "1_1") (pintype "passive"))
      (node (ref "C172") (pin "1") (pinfunction "1_1") (pintype "passive"))
      (node (ref "C173") (pin "1") (pinfunction "1_1") (pintype "passive"))
      (node (ref "C178") (pin "1") (pinfunction "1_1") (pintype "passive"))
      (node (ref "C179") (pin "1") (pinfunction "1_1") (pintype "passive"))
      (node (ref "C180") (pin "1") (pinfunction "1_1") (pintype "passive"))
      (node (ref "C181") (pin "1") (pinfunction "1_1") (pintype "passive"))
      (node (ref "C184") (pin "1") (pinfunction "1_1") (pintype "passive"))
      (node (ref "C185") (pin "1") (pinfunction "1_1") (pintype "passive"))
      (node (ref "U24") (pin "1") (pinfunction "1DIR_1") (pintype "passive"))
      (node (ref "U24") (pin "24") (pinfunction "2DIR_24") (pintype "passive"))
      (node (ref "U24") (pin "31") (pinfunction "VCCA_1_31") (pintype "passive"))
      (node (ref "U24") (pin "42") (pinfunction "VCCA_2_42") (pintype "passive"))
      (node (ref "U25") (pin "31") (pinfunction "VCCA_1_31") (pintype "passive"))
      (node (ref "U25") (pin "42") (pinfunction "VCCA_2_42") (pintype "passive"))
      (node (ref "U26") (pin "31") (pinfunction "VCCA_1_31") (pintype "passive"))
      (node (ref "U26") (pin "42") (pinfunction "VCCA_2_42") (pintype "passive"))
      (node (ref "U27") (pin "1") (pinfunction "1DIR_1") (pintype "passive"))
      (node (ref "U27") (pin "24") (pinfunction "2DIR_24") (pintype "passive"))
      (node (ref "U27") (pin "31") (pinfunction "VCCA_1_31") (pintype "passive"))
      (node (ref "U27") (pin "42") (pinfunction "VCCA_2_42") (pintype "passive"))
      (node (ref "U28") (pin "31") (pinfunction "VCCA_1_31") (pintype "passive"))
      (node (ref "U28") (pin "42") (pinfunction "VCCA_2_42") (pintype "passive"))
    )
    (net (code "171") (name "GND") (class "Default")
      (node (ref "C166") (pin "2") (pinfunction "2_2") (pintype "passive"))
      (node (ref "C167") (pin "2") (pinfunction "2_2") (pintype "passive"))
      (node (ref "C168") (pin "2") (pinfunction "2_2") (pintype "passive"))
      (node (ref "C169") (pin "2") (pinfunction "2_2") (pintype "passive"))
      (node (ref "C170") (pin "2") (pinfunction "2_2") (pintype "passive"))
      (node (ref "C171") (pin "2") (pinfunction "2_2") (pintype "passive"))
      (node (ref "C172") (pin "2") (pinfunction "2_2") (pintype "passive"))
      (node (ref "C173") (pin "2") (pinfunction "2_2") (pintype "passive"))
      (node (ref "C174") (pin "2") (pinfunction "2_2") (pintype "passive"))
      (node (ref "C175") (pin "2") (pinfunction "2_2") (pintype "passive"))
      (node (ref "C176") (pin "2") (pinfunction "2_2") (pintype "passive"))
      (node (ref "C177") (pin "2") (pinfunction "2_2") (pintype "passive"))
      (node (ref "C178") (pin "2") (pinfunction "2_2") (pintype "passive"))
      (node (ref "C179") (pin "2") (pinfunction "2_2") (pintype "passive"))
      (node (ref "C180") (pin "2") (pinfunction "2_2") (pintype "passive"))
      (node (ref "C181") (pin "2") (pinfunction "2_2") (pintype "passive"))
      (node (ref "C182") (pin "2") (pinfunction "2_2") (pintype "passive"))
      (node (ref "C183") (pin "2") (pinfunction "2_2") (pintype "passive"))
      (node (ref "C184") (pin "2") (pinfunction "2_2") (pintype "passive"))
      (node (ref "C185") (pin "2") (pinfunction "2_2") (pintype "passive"))
      (node (ref "U24") (pin "10") (pinfunction "GND_2_10") (pintype "passive"))
      (node (ref "U24") (pin "15") (pinfunction "GND_3_15") (pintype "passive"))
      (node (ref "U24") (pin "21") (pinfunction "GND_4_21") (pintype "passive"))
      (node (ref "U24") (pin "28") (pinfunction "GND_5_28") (pintype "passive"))
      (node (ref "U24") (pin "34") (pinfunction "GND_6_34") (pintype "passive"))
      (node (ref "U24") (pin "39") (pinfunction "GND_7_39") (pintype "passive"))
      (node (ref "U24") (pin "4") (pinfunction "GND_1_4") (pintype "passive"))
      (node (ref "U24") (pin "45") (pinfunction "GND_8_45") (pintype "passive"))
      (node (ref "U25") (pin "1") (pinfunction "1DIR_1") (pintype "passive"))
      (node (ref "U25") (pin "10") (pinfunction "GND_2_10") (pintype "passive"))
      (node (ref "U25") (pin "15") (pinfunction "GND_3_15") (pintype "passive"))
      (node (ref "U25") (pin "21") (pinfunction "GND_4_21") (pintype "passive"))
      (node (ref "U25") (pin "24") (pinfunction "2DIR_24") (pintype "passive"))
      (node (ref "U25") (pin "28") (pinfunction "GND_5_28") (pintype "passive"))
      (node (ref "U25") (pin "34") (pinfunction "GND_6_34") (pintype "passive"))
      (node (ref "U25") (pin "39") (pinfunction "GND_7_39") (pintype "passive"))
      (node (ref "U25") (pin "4") (pinfunction "GND_1_4") (pintype "passive"))
      (node (ref "U25") (pin "45") (pinfunction "GND_8_45") (pintype "passive"))
      (node (ref "U26") (pin "10") (pinfunction "GND_2_10") (pintype "passive"))
      (node (ref "U26") (pin "15") (pinfunction "GND_3_15") (pintype "passive"))
      (node (ref "U26") (pin "21") (pinfunction "GND_4_21") (pintype "passive"))
      (node (ref "U26") (pin "28") (pinfunction "GND_5_28") (pintype "passive"))
      (node (ref "U26") (pin "34") (pinfunction "GND_6_34") (pintype "passive"))
      (node (ref "U26") (pin "39") (pinfunction "GND_7_39") (pintype "passive"))
      (node (ref "U26") (pin "4") (pinfunction "GND_1_4") (pintype "passive"))
      (node (ref "U26") (pin "45") (pinfunction "GND_8_45") (pintype "passive"))
      (node (ref "U27") (pin "10") (pinfunction "GND_2_10") (pintype "passive"))
      (node (ref "U27") (pin "15") (pinfunction "GND_3_15") (pintype "passive"))
      (node (ref "U27") (pin "21") (pinfunction "GND_4_21") (pintype "passive"))
      (node (ref "U27") (pin "28") (pinfunction "GND_5_28") (pintype "passive"))
      (node (ref "U27") (pin "34") (pinfunction "GND_6_34") (pintype "passive"))
      (node (ref "U27") (pin "39") (pinfunction "GND_7_39") (pintype "passive"))
      (node (ref "U27") (pin "4") (pinfunction "GND_1_4") (pintype "passive"))
      (node (ref "U27") (pin "45") (pinfunction "GND_8_45") (pintype "passive"))
      (node (ref "U28") (pin "10") (pinfunction "GND_2_10") (pintype "passive"))
      (node (ref "U28") (pin "15") (pinfunction "GND_3_15") (pintype "passive"))
      (node (ref "U28") (pin "21") (pinfunction "GND_4_21") (pintype "passive"))
      (node (ref "U28") (pin "28") (pinfunction "GND_5_28") (pintype "passive"))
      (node (ref "U28") (pin "34") (pinfunction "GND_6_34") (pintype "passive"))
      (node (ref "U28") (pin "39") (pinfunction "GND_7_39") (pintype "passive"))
      (node (ref "U28") (pin "4") (pinfunction "GND_1_4") (pintype "passive"))
      (node (ref "U28") (pin "45") (pinfunction "GND_8_45") (pintype "passive"))
    )
    (net (code "172") (name "IN_5V0") (class "Default")
      (node (ref "C166") (pin "1") (pinfunction "1_1") (pintype "passive"))
      (node (ref "C167") (pin "1") (pinfunction "1_1") (pintype "passive"))
      (node (ref "C168") (pin "1") (pinfunction "1_1") (pintype "passive"))
      (node (ref "C169") (pin "1") (pinfunction "1_1") (pintype "passive"))
      (node (ref "C174") (pin "1") (pinfunction "1_1") (pintype "passive"))
      (node (ref "C175") (pin "1") (pinfunction "1_1") (pintype "passive"))
      (node (ref "C176") (pin "1") (pinfunction "1_1") (pintype "passive"))
      (node (ref "C177") (pin "1") (pinfunction "1_1") (pintype "passive"))
      (node (ref "C182") (pin "1") (pinfunction "1_1") (pintype "passive"))
      (node (ref "C183") (pin "1") (pinfunction "1_1") (pintype "passive"))
      (node (ref "U24") (pin "18") (pinfunction "VCCB_2_18") (pintype "passive"))
      (node (ref "U24") (pin "7") (pinfunction "VCCB_1_7") (pintype "passive"))
      (node (ref "U25") (pin "18") (pinfunction "VCCB_2_18") (pintype "passive"))
      (node (ref "U25") (pin "7") (pinfunction "VCCB_1_7") (pintype "passive"))
      (node (ref "U26") (pin "18") (pinfunction "VCCB_2_18") (pintype "passive"))
      (node (ref "U26") (pin "7") (pinfunction "VCCB_1_7") (pintype "passive"))
      (node (ref "U27") (pin "18") (pinfunction "VCCB_2_18") (pintype "passive"))
      (node (ref "U27") (pin "7") (pinfunction "VCCB_1_7") (pintype "passive"))
      (node (ref "U28") (pin "18") (pinfunction "VCCB_2_18") (pintype "passive"))
      (node (ref "U28") (pin "7") (pinfunction "VCCB_1_7") (pintype "passive"))
    )
  )
)
